# Schematic_Node.net
KiCad netlist of a schematic drawn in Altium Designer
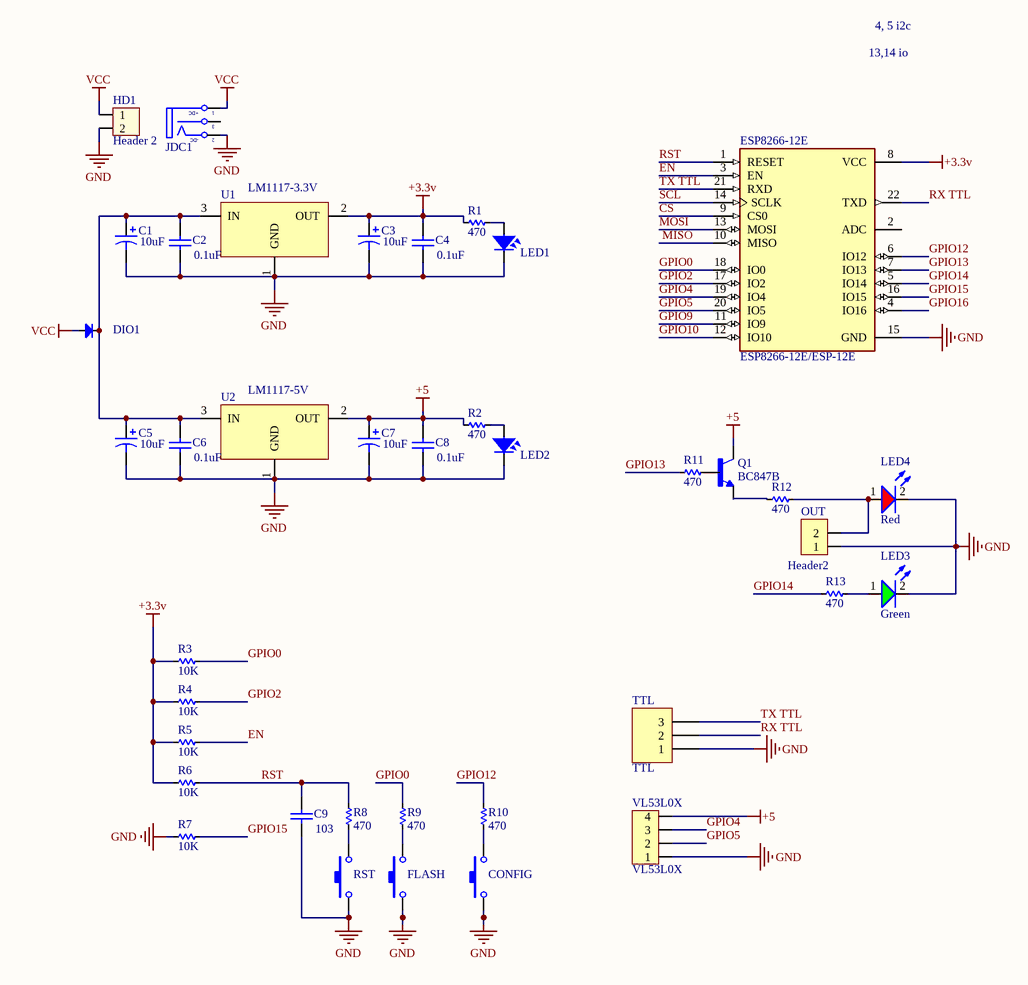
[diagram p0: Schematic_Node.SchDoc]

(export (version "E")
  (design (tool "Eeschema 10.0.6"))
  (components
    (comp (ref "C1")
      (value "10uF")
      (footprint "C0805")
      (description "Polarized Capacitor (Surface Mount)")
      (fields (field (name "Comment") "Cap Pol3") (field (name "PUBLISHER") "Altium Limited"))
      (libsource (lib "Miscellaneous Devices") (part "Cap Pol3"))
    )
    (comp (ref "C2")
      (value "0.1uF")
      (footprint "C1206")
      (description "Capacitor (Semiconductor SIM Model)")
      (fields (field (name "PUBLISHER") "Altium Limited"))
      (libsource (lib "Miscellaneous Devices") (part "Cap Semi"))
    )
    (comp (ref "C3")
      (value "10uF")
      (footprint "C0805")
      (description "Polarized Capacitor (Surface Mount)")
      (fields (field (name "Comment") "Cap Pol3") (field (name "PUBLISHER") "Altium Limited"))
      (libsource (lib "Miscellaneous Devices") (part "Cap Pol3"))
    )
    (comp (ref "C4")
      (value "0.1uF")
      (footprint "C1206")
      (description "Capacitor (Semiconductor SIM Model)")
      (fields (field (name "Comment") "Cap Semi") (field (name "PUBLISHER") "Altium Limited"))
      (libsource (lib "Miscellaneous Devices") (part "Cap Semi"))
    )
    (comp (ref "C5")
      (value "10uF")
      (footprint "C0805")
      (description "Polarized Capacitor (Surface Mount)")
      (fields (field (name "Comment") "Cap Pol3") (field (name "PUBLISHER") "Altium Limited"))
      (libsource (lib "Miscellaneous Devices") (part "Cap Pol3"))
    )
    (comp (ref "C6")
      (value "0.1uF")
      (footprint "C1206")
      (description "Capacitor (Semiconductor SIM Model)")
      (fields (field (name "PUBLISHER") "Altium Limited"))
      (libsource (lib "Miscellaneous Devices") (part "Cap Semi"))
    )
    (comp (ref "C7")
      (value "10uF")
      (footprint "C0805")
      (description "Polarized Capacitor (Surface Mount)")
      (fields (field (name "Comment") "Cap Pol3") (field (name "PUBLISHER") "Altium Limited"))
      (libsource (lib "Miscellaneous Devices") (part "Cap Pol3"))
    )
    (comp (ref "C8")
      (value "0.1uF")
      (footprint "C1206")
      (description "Capacitor (Semiconductor SIM Model)")
      (fields (field (name "Comment") "Cap Semi") (field (name "PUBLISHER") "Altium Limited"))
      (libsource (lib "Miscellaneous Devices") (part "Cap Semi"))
    )
    (comp (ref "C9")
      (value "103")
      (footprint "C1206")
      (description "Capacitor (Semiconductor SIM Model)")
      (fields (field (name "Comment") "Cap Semi") (field (name "PUBLISHER") "Altium Limited"))
      (libsource (lib "Miscellaneous Devices") (part "Cap Semi"))
    )
    (comp (ref "CONFIG")
      (value "SW-SMD")
      (footprint "SW-SMD")
      (description "Switch")
      (fields (field (name "PUBLISHER") "Altium Limited"))
      (libsource (lib "TechMT.VN_Lib_Project v1.0") (part "SW-SMD"))
    )
    (comp (ref "DIO1")
      (value "Diode SMD")
      (footprint "DIO-SMD-106")
      (description "Default Diode")
      (fields (field (name "PUBLISHER") "Altium Limited"))
      (libsource (lib "TechMT.VN_Lib_Project v2") (part "Diode SMD"))
    )
    (comp (ref "ESP8266-12E")
      (value "ESP8266-12E/ESP-12E")
      (footprint "XCVR_ESP8266-12E/ESP-12E")
      (fields (field (name "MF") "AI-Thinker"))
      (libsource (lib "ESP8266-12E_ESP-12E") (part "ESP8266-12E/ESP-12E"))
    )
    (comp (ref "FLASH")
      (value "SW-SMD")
      (footprint "SW-SMD")
      (description "Switch")
      (fields (field (name "PUBLISHER") "Altium Limited"))
      (libsource (lib "TechMT.VN_Lib_Project v1.0") (part "SW-SMD"))
    )
    (comp (ref "HD1")
      (value "Header 2")
      (footprint "HED2")
      (description "Header 2 (Green)")
      (libsource (lib "syhaunguyen") (part "Hed2"))
    )
    (comp (ref "JDC1")
      (value "Jack DC")
      (footprint "DC-IN")
      (description "Jack DC input")
      (libsource (lib "TechMT.VN_Lib_Project v1.0") (part "Jack DC"))
    )
    (comp (ref "LED1")
      (value "LED")
      (footprint "LED-1206-Red")
      (libsource (lib "TechMT.VN_Lib_Project v2") (part "LED SMD"))
    )
    (comp (ref "LED2")
      (value "LED")
      (footprint "LED-1206-Red")
      (libsource (lib "TechMT.VN_Lib_Project v2") (part "LED SMD"))
    )
    (comp (ref "LED3")
      (value "Green")
      (footprint "LED-GREEN-0805")
      (description "LED Green 2mA 3V 0805")
      (fields (field (name "Comment") "LED-Green"))
      (libsource (lib "TechMT.VN_Lib_Project v2") (part "LED-Green"))
    )
    (comp (ref "LED4")
      (value "Red")
      (footprint "LED-RED-0805")
      (description "LED Red 2mA 1.8V 0805")
      (fields (field (name "Comment") "LED-Red"))
      (libsource (lib "TechMT.VN_Lib_Project v2") (part "Led-Red"))
    )
    (comp (ref "OUT")
      (value "Header2")
      (footprint "HDR2")
      (description "Header IDC, 2 x 1 Pin Vertical 2.54mm Pitch (Non-Boxed, Male)")
      (fields
        (field (name "MANUFACTURER") "Würth Elektronik eiSos GmbH")
        (field (name "PARTNO") "613002143121")
        (field (name "CREATED BY") "Karrer Zheng")
      )
      (libsource (lib "TechMT.VN_Lib_Project v2") (part "Header2"))
    )
    (comp (ref "Q1")
      (value "BC847B")
      (footprint "SOT100P230X110-3N")
      (description "Bipolar (BJT) Transistor NPN 45V 100mA 100MHz 150mW Surface Mount SOT-523")
      (fields (field (name "MF") "STMicroelectronics"))
      (libsource (lib "BC847B") (part "BC847B"))
    )
    (comp (ref "R1")
      (value "470")
      (footprint "RES-SMD-1206")
      (description "Resistor")
      (fields
        (field (name "MANUFACTURER") "Generic Components")
        (field (name "PUBLISHER") "Altium Hobart Technology Centre")
      )
      (libsource (lib "TechMT.VN_Lib_Project v2") (part "Res-SMD"))
    )
    (comp (ref "R2")
      (value "470")
      (footprint "RES-SMD-1206")
      (description "Resistor")
      (fields
        (field (name "MANUFACTURER") "Generic Components")
        (field (name "PUBLISHER") "Altium Hobart Technology Centre")
      )
      (libsource (lib "TechMT.VN_Lib_Project v2") (part "Res-SMD"))
    )
    (comp (ref "R3")
      (value "10K")
      (footprint "RES-SMD-1206")
      (description "Resistor")
      (fields
        (field (name "MANUFACTURER") "Generic Components")
        (field (name "PUBLISHER") "Altium Hobart Technology Centre")
      )
      (libsource (lib "TechMT.VN_Lib_Project v2") (part "Res-SMD"))
    )
    (comp (ref "R4")
      (value "10K")
      (footprint "RES-SMD-1206")
      (description "Resistor")
      (fields
        (field (name "MANUFACTURER") "Generic Components")
        (field (name "PUBLISHER") "Altium Hobart Technology Centre")
      )
      (libsource (lib "TechMT.VN_Lib_Project v2") (part "Res-SMD"))
    )
    (comp (ref "R5")
      (value "10K")
      (footprint "RES-SMD-1206")
      (description "Resistor")
      (fields
        (field (name "MANUFACTURER") "Generic Components")
        (field (name "PUBLISHER") "Altium Hobart Technology Centre")
      )
      (libsource (lib "TechMT.VN_Lib_Project v2") (part "Res-SMD"))
    )
    (comp (ref "R6")
      (value "10K")
      (footprint "RES-SMD-1206")
      (description "Resistor")
      (fields
        (field (name "MANUFACTURER") "Generic Components")
        (field (name "PUBLISHER") "Altium Hobart Technology Centre")
      )
      (libsource (lib "TechMT.VN_Lib_Project v2") (part "Res-SMD"))
    )
    (comp (ref "R7")
      (value "10K")
      (footprint "RES-SMD-1206")
      (description "Resistor")
      (fields
        (field (name "MANUFACTURER") "Generic Components")
        (field (name "PUBLISHER") "Altium Hobart Technology Centre")
      )
      (libsource (lib "TechMT.VN_Lib_Project v2") (part "Res-SMD"))
    )
    (comp (ref "R8")
      (value "470")
      (footprint "RES-SMD-1206")
      (description "Resistor")
      (fields
        (field (name "MANUFACTURER") "Generic Components")
        (field (name "PUBLISHER") "Altium Hobart Technology Centre")
      )
      (libsource (lib "TechMT.VN_Lib_Project v2") (part "Res-SMD"))
    )
    (comp (ref "R9")
      (value "470")
      (footprint "RES-SMD-1206")
      (description "Resistor")
      (fields
        (field (name "MANUFACTURER") "Generic Components")
        (field (name "PUBLISHER") "Altium Hobart Technology Centre")
      )
      (libsource (lib "TechMT.VN_Lib_Project v2") (part "Res-SMD"))
    )
    (comp (ref "R10")
      (value "470")
      (footprint "RES-SMD-1206")
      (description "Resistor")
      (fields
        (field (name "MANUFACTURER") "Generic Components")
        (field (name "PUBLISHER") "Altium Hobart Technology Centre")
      )
      (libsource (lib "TechMT.VN_Lib_Project v2") (part "Res-SMD"))
    )
    (comp (ref "R11")
      (value "470")
      (footprint "RES-SMD-1206")
      (description "Resistor")
      (fields
        (field (name "MANUFACTURER") "Generic Components")
        (field (name "PUBLISHER") "Altium Hobart Technology Centre")
      )
      (libsource (lib "TechMT.VN_Lib_Project v2") (part "Res-SMD"))
    )
    (comp (ref "R12")
      (value "470")
      (footprint "RES-SMD-1206")
      (description "Resistor")
      (fields
        (field (name "MANUFACTURER") "Generic Components")
        (field (name "PUBLISHER") "Altium Hobart Technology Centre")
      )
      (libsource (lib "TechMT.VN_Lib_Project v2") (part "Res-SMD"))
    )
    (comp (ref "R13")
      (value "470")
      (footprint "RES-SMD-1206")
      (description "Resistor")
      (fields
        (field (name "MANUFACTURER") "Generic Components")
        (field (name "PUBLISHER") "Altium Hobart Technology Centre")
      )
      (libsource (lib "TechMT.VN_Lib_Project v2") (part "Res-SMD"))
    )
    (comp (ref "RST")
      (value "SW-SMD")
      (footprint "SW-SMD")
      (description "Switch")
      (fields (field (name "PUBLISHER") "Altium Limited"))
      (libsource (lib "TechMT.VN_Lib_Project v1.0") (part "SW-SMD"))
    )
    (comp (ref "TTL")
      (value "TTL")
      (footprint "HDR1X3")
      (description "Header, 3-Pin")
      (fields (field (name "PUBLISHER") "Altium Limited"))
      (libsource (lib "Miscellaneous Connectors") (part "Header 3"))
    )
    (comp (ref "U1")
      (value "LM1117-3.3V")
      (footprint "SOT223")
      (description "800mA Low-Dropout Linear Regulator")
      (fields (field (name "CREATOR") "Nguyen Ba Bien"))
      (libsource (lib "TechMT.VN_Lib_Project v2") (part "LM1117"))
    )
    (comp (ref "U2")
      (value "LM1117-5V")
      (footprint "SOT223")
      (description "800mA Low-Dropout Linear Regulator")
      (fields (field (name "CREATOR") "Nguyen Ba Bien"))
      (libsource (lib "TechMT.VN_Lib_Project v2") (part "LM1117"))
    )
    (comp (ref "VL53L0X")
      (value "VL53L0X")
      (footprint "HDR4")
      (description "Header IDC, 4 x 1 Pin Vertical 2.54mm Pitch (Non-Boxed, Male)")
      (fields
        (field (name "MANUFACTURER") "Würth Elektronik eiSos GmbH")
        (field (name "PARTNO") "613002143121")
        (field (name "CREATED BY") "Karrer Zheng")
      )
      (libsource (lib "TechMT.VN_Lib_Project v2") (part "Header4"))
    )
  )
  (nets
    (net (code "1") (name "+3.3v") (class "Default")
      (node (ref "C3") (pin "1") (pinfunction "1_1") (pintype "passive"))
      (node (ref "C4") (pin "2") (pinfunction "2_2") (pintype "passive"))
      (node (ref "ESP8266-12E") (pin "8") (pinfunction "VCC_8") (pintype "power_in"))
      (node (ref "R1") (pin "2") (pinfunction "2_2") (pintype "passive"))
      (node (ref "R3") (pin "2") (pinfunction "2_2") (pintype "passive"))
      (node (ref "R4") (pin "2") (pinfunction "2_2") (pintype "passive"))
      (node (ref "R5") (pin "2") (pinfunction "2_2") (pintype "passive"))
      (node (ref "R6") (pin "2") (pinfunction "2_2") (pintype "passive"))
      (node (ref "U1") (pin "2") (pinfunction "OUT_2") (pintype "passive"))
    )
    (net (code "2") (name "+5") (class "Default")
      (node (ref "C7") (pin "1") (pinfunction "1_1") (pintype "passive"))
      (node (ref "C8") (pin "2") (pinfunction "2_2") (pintype "passive"))
      (node (ref "Q1") (pin "3") (pinfunction "C_3") (pintype "passive"))
      (node (ref "R2") (pin "2") (pinfunction "2_2") (pintype "passive"))
      (node (ref "U2") (pin "2") (pinfunction "OUT_2") (pintype "passive"))
      (node (ref "VL53L0X") (pin "4") (pinfunction "4_4") (pintype "passive"))
    )
    (net (code "3") (name "/CS") (class "Default")
      (node (ref "ESP8266-12E") (pin "9") (pinfunction "CS0_9") (pintype "input"))
    )
    (net (code "4") (name "/EN") (class "Default")
      (node (ref "ESP8266-12E") (pin "3") (pinfunction "EN_3") (pintype "input"))
      (node (ref "R5") (pin "1") (pinfunction "1_1") (pintype "passive"))
    )
    (net (code "5") (name "/GPIO0") (class "Default")
      (node (ref "ESP8266-12E") (pin "18") (pinfunction "IO0_18") (pintype "bidirectional"))
      (node (ref "R3") (pin "1") (pinfunction "1_1") (pintype "passive"))
      (node (ref "R9") (pin "1") (pinfunction "1_1") (pintype "passive"))
    )
    (net (code "6") (name "/GPIO2") (class "Default")
      (node (ref "ESP8266-12E") (pin "17") (pinfunction "IO2_17") (pintype "bidirectional"))
      (node (ref "R4") (pin "1") (pinfunction "1_1") (pintype "passive"))
    )
    (net (code "7") (name "/GPIO4") (class "Default")
      (node (ref "ESP8266-12E") (pin "19") (pinfunction "IO4_19") (pintype "bidirectional"))
      (node (ref "VL53L0X") (pin "3") (pinfunction "3_3") (pintype "passive"))
    )
    (net (code "8") (name "/GPIO5") (class "Default")
      (node (ref "ESP8266-12E") (pin "20") (pinfunction "IO5_20") (pintype "bidirectional"))
      (node (ref "VL53L0X") (pin "2") (pinfunction "2_2") (pintype "passive"))
    )
    (net (code "9") (name "/GPIO9") (class "Default")
      (node (ref "ESP8266-12E") (pin "11") (pinfunction "IO9_11") (pintype "bidirectional"))
    )
    (net (code "10") (name "/GPIO10") (class "Default")
      (node (ref "ESP8266-12E") (pin "12") (pinfunction "IO10_12") (pintype "bidirectional"))
    )
    (net (code "11") (name "/GPIO12") (class "Default")
      (node (ref "ESP8266-12E") (pin "6") (pinfunction "IO12_6") (pintype "bidirectional"))
      (node (ref "R10") (pin "1") (pinfunction "1_1") (pintype "passive"))
    )
    (net (code "12") (name "/GPIO13") (class "Default")
      (node (ref "ESP8266-12E") (pin "7") (pinfunction "IO13_7") (pintype "bidirectional"))
      (node (ref "R11") (pin "2") (pinfunction "2_2") (pintype "passive"))
    )
    (net (code "13") (name "/GPIO14") (class "Default")
      (node (ref "ESP8266-12E") (pin "5") (pinfunction "IO14_5") (pintype "bidirectional"))
      (node (ref "R13") (pin "2") (pinfunction "2_2") (pintype "passive"))
    )
    (net (code "14") (name "/GPIO15") (class "Default")
      (node (ref "ESP8266-12E") (pin "16") (pinfunction "IO15_16") (pintype "bidirectional"))
      (node (ref "R7") (pin "1") (pinfunction "1_1") (pintype "passive"))
    )
    (net (code "15") (name "/GPIO16") (class "Default")
      (node (ref "ESP8266-12E") (pin "4") (pinfunction "IO16_4") (pintype "bidirectional"))
    )
    (net (code "16") (name "/MOSI") (class "Default")
      (node (ref "ESP8266-12E") (pin "13") (pinfunction "MOSI_13") (pintype "bidirectional"))
    )
    (net (code "17") (name "/RST") (class "Default")
      (node (ref "C9") (pin "2") (pinfunction "2_2") (pintype "passive"))
      (node (ref "ESP8266-12E") (pin "1") (pinfunction "RESET_1") (pintype "input"))
      (node (ref "R6") (pin "1") (pinfunction "1_1") (pintype "passive"))
      (node (ref "R8") (pin "1") (pinfunction "1_1") (pintype "passive"))
    )
    (net (code "18") (name "/RX TTL") (class "Default")
      (node (ref "ESP8266-12E") (pin "22") (pinfunction "TXD_22") (pintype "output"))
      (node (ref "TTL") (pin "2") (pinfunction "2_2") (pintype "passive"))
    )
    (net (code "19") (name "/SCL") (class "Default")
      (node (ref "ESP8266-12E") (pin "14") (pinfunction "SCLK_14") (pintype "input"))
    )
    (net (code "20") (name "/TX TTL") (class "Default")
      (node (ref "ESP8266-12E") (pin "21") (pinfunction "RXD_21") (pintype "input"))
      (node (ref "TTL") (pin "3") (pinfunction "3_3") (pintype "passive"))
    )
    (net (code "21") (name "/MISO") (class "Default")
      (node (ref "ESP8266-12E") (pin "10") (pinfunction "MISO_10") (pintype "bidirectional"))
    )
    (net (code "22") (name "GND") (class "Default")
      (node (ref "C1") (pin "2") (pinfunction "2_2") (pintype "passive"))
      (node (ref "C2") (pin "1") (pinfunction "1_1") (pintype "passive"))
      (node (ref "C3") (pin "2") (pinfunction "2_2") (pintype "passive"))
      (node (ref "C4") (pin "1") (pinfunction "1_1") (pintype "passive"))
      (node (ref "C5") (pin "2") (pinfunction "2_2") (pintype "passive"))
      (node (ref "C6") (pin "1") (pinfunction "1_1") (pintype "passive"))
      (node (ref "C7") (pin "2") (pinfunction "2_2") (pintype "passive"))
      (node (ref "C8") (pin "1") (pinfunction "1_1") (pintype "passive"))
      (node (ref "C9") (pin "1") (pinfunction "1_1") (pintype "passive"))
      (node (ref "CONFIG") (pin "1") (pinfunction "1_1") (pintype "passive"))
      (node (ref "ESP8266-12E") (pin "15") (pinfunction "GND_15") (pintype "power_in"))
      (node (ref "FLASH") (pin "1") (pinfunction "1_1") (pintype "passive"))
      (node (ref "HD1") (pin "2") (pinfunction "2_2") (pintype "passive"))
      (node (ref "JDC1") (pin "2") (pinfunction "TN_2") (pintype "passive"))
      (node (ref "LED1") (pin "2") (pinfunction "2_2") (pintype "passive"))
      (node (ref "LED2") (pin "2") (pinfunction "2_2") (pintype "passive"))
      (node (ref "LED3") (pin "2") (pinfunction "K_2") (pintype "passive"))
      (node (ref "LED4") (pin "2") (pinfunction "K_2") (pintype "passive"))
      (node (ref "OUT") (pin "1") (pinfunction "1_1") (pintype "passive"))
      (node (ref "R7") (pin "2") (pinfunction "2_2") (pintype "passive"))
      (node (ref "RST") (pin "1") (pinfunction "1_1") (pintype "passive"))
      (node (ref "TTL") (pin "1") (pinfunction "1_1") (pintype "passive"))
      (node (ref "U1") (pin "1") (pinfunction "GND_1") (pintype "passive"))
      (node (ref "U2") (pin "1") (pinfunction "GND_1") (pintype "passive"))
      (node (ref "VL53L0X") (pin "1") (pinfunction "1_1") (pintype "passive"))
    )
    (net (code "23") (name "Net-(CONFIG-Pad2)") (class "Default")
      (node (ref "CONFIG") (pin "2") (pinfunction "2_2") (pintype "passive"))
      (node (ref "R10") (pin "2") (pinfunction "2_2") (pintype "passive"))
    )
    (net (code "24") (name "Net-(DIO1-K)") (class "Default")
      (node (ref "C1") (pin "1") (pinfunction "1_1") (pintype "passive"))
      (node (ref "C2") (pin "2") (pinfunction "2_2") (pintype "passive"))
      (node (ref "C5") (pin "1") (pinfunction "1_1") (pintype "passive"))
      (node (ref "C6") (pin "2") (pinfunction "2_2") (pintype "passive"))
      (node (ref "DIO1") (pin "2") (pinfunction "K_2") (pintype "passive"))
      (node (ref "U1") (pin "3") (pinfunction "IN_3") (pintype "passive"))
      (node (ref "U2") (pin "3") (pinfunction "IN_3") (pintype "passive"))
    )
    (net (code "25") (name "Net-(FLASH-Pad2)") (class "Default")
      (node (ref "FLASH") (pin "2") (pinfunction "2_2") (pintype "passive"))
      (node (ref "R9") (pin "2") (pinfunction "2_2") (pintype "passive"))
    )
    (net (code "26") (name "Net-(LED1-Pad1)") (class "Default")
      (node (ref "LED1") (pin "1") (pinfunction "1_1") (pintype "passive"))
      (node (ref "R1") (pin "1") (pinfunction "1_1") (pintype "passive"))
    )
    (net (code "27") (name "Net-(LED2-Pad1)") (class "Default")
      (node (ref "LED2") (pin "1") (pinfunction "1_1") (pintype "passive"))
      (node (ref "R2") (pin "1") (pinfunction "1_1") (pintype "passive"))
    )
    (net (code "28") (name "Net-(LED3-A)") (class "Default")
      (node (ref "LED3") (pin "1") (pinfunction "A_1") (pintype "passive"))
      (node (ref "R13") (pin "1") (pinfunction "1_1") (pintype "passive"))
    )
    (net (code "29") (name "Net-(LED4-A)") (class "Default")
      (node (ref "LED4") (pin "1") (pinfunction "A_1") (pintype "passive"))
      (node (ref "OUT") (pin "2") (pinfunction "2_2") (pintype "passive"))
      (node (ref "R12") (pin "1") (pinfunction "1_1") (pintype "passive"))
    )
    (net (code "30") (name "Net-(Q1-B)") (class "Default")
      (node (ref "Q1") (pin "1") (pinfunction "B_1") (pintype "passive"))
      (node (ref "R11") (pin "1") (pinfunction "1_1") (pintype "passive"))
    )
    (net (code "31") (name "Net-(Q1-E)") (class "Default")
      (node (ref "Q1") (pin "2") (pinfunction "E_2") (pintype "passive"))
      (node (ref "R12") (pin "2") (pinfunction "2_2") (pintype "passive"))
    )
    (net (code "32") (name "Net-(R8-Pad2)") (class "Default")
      (node (ref "R8") (pin "2") (pinfunction "2_2") (pintype "passive"))
      (node (ref "RST") (pin "2") (pinfunction "2_2") (pintype "passive"))
    )
    (net (code "33") (name "VCC") (class "Default")
      (node (ref "DIO1") (pin "1") (pinfunction "A_1") (pintype "passive"))
      (node (ref "HD1") (pin "1") (pinfunction "1_1") (pintype "passive"))
      (node (ref "JDC1") (pin "1") (pinfunction "T_1") (pintype "passive"))
    )
    (net (code "34") (name "unconnected-(ESP8266-12E-ADC-Pad2)") (class "Default")
      (node (ref "ESP8266-12E") (pin "2") (pinfunction "ADC_2") (pintype "passive"))
    )
    (net (code "35") (name "unconnected-(JDC1-S-Pad3)") (class "Default")
      (node (ref "JDC1") (pin "3") (pinfunction "S_3") (pintype "power_in"))
    )
  )
)
